# Power_System.net
KiCad netlist of a schematic drawn in Altium Designer
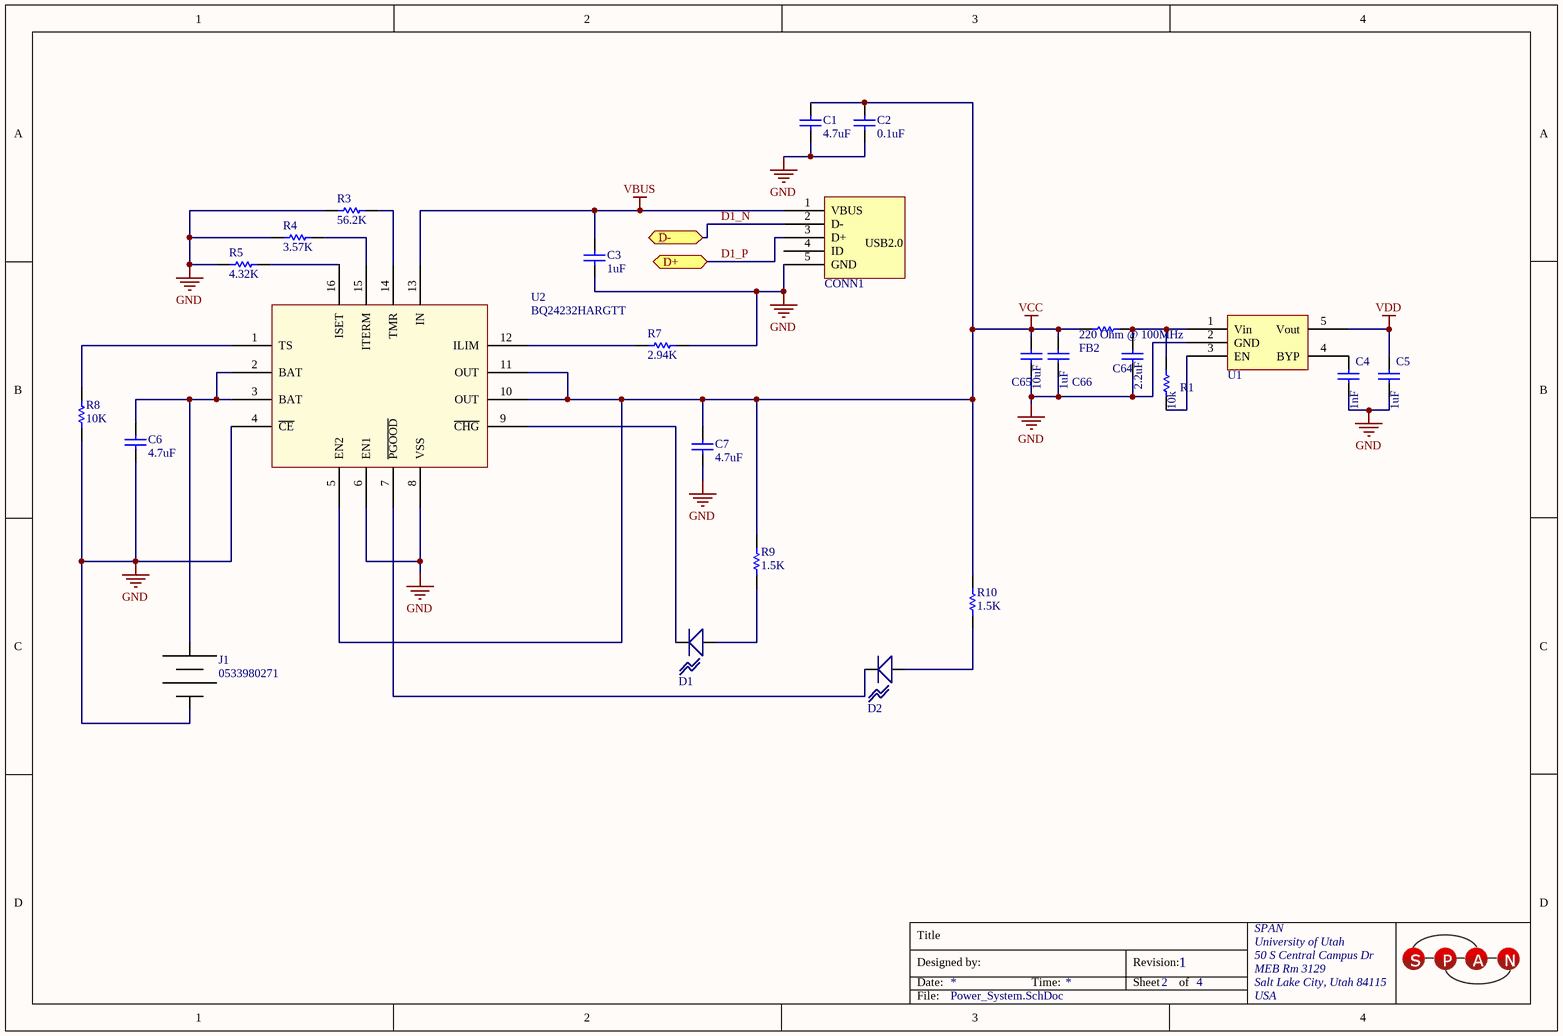
[diagram p0: Power_System.SchDoc]

(export (version "E")
  (design (tool "Eeschema 10.0.6"))
  (components
    (comp (ref "C1")
      (value "4.7uF")
      (footprint "0603_Cap")
      (fields
        (field (name "MANUFACTURER") "Taiyo Yuden")
        (field (name "MANUFACTURER PART NUMBER") "JMK107BJ475MAHT")
        (field (name "TOLERANCE") "±20%")
      )
      (libsource (lib "Sitara") (part "JMK107BJ475MAHT"))
    )
    (comp (ref "C2")
      (value "0.1uF")
      (footprint "0603_Cap")
      (description "CAP CER 0.1UF 16V X7R 0603")
      (fields
        (field (name "MANUFACTURER") "AVX Corporation")
        (field (name "MANUFACTURER PART NUMBER") "0603YC104KAT4A")
      )
      (libsource (lib "Sitara") (part "0603YC104KAT4A"))
    )
    (comp (ref "C3")
      (value "1uF")
      (footprint "0603_Cap")
      (description "CAP CER 1uF SMD")
      (fields
        (field (name "MANUFACTURER") "Taiyo Yuden")
        (field (name "MANUFACTURER PART NUMBER") "JMK107C6105KA-T")
      )
      (libsource (lib "Sitara") (part "JMK107C6105KA-T"))
    )
    (comp (ref "C4")
      (value "10uF")
      (footprint "0603_Cap")
      (description "CAP CER 1000PF 50V 5% NP0 0603")
      (fields
        (field (name "MANUFACTURER") "Murata Electronics North America")
        (field (name "MANUFACTURER PART NUMBER") "GRM1885C1H102JA01D")
      )
      (libsource (lib "Sara") (part "GRM1885C1H102JA01D"))
    )
    (comp (ref "C5")
      (value "GRM188R61A105KA61D")
      (footprint "CAPC1608X08N (0603)")
      (description "CAP CER 1UF 10V 10% X5R 0603")
      (fields
        (field (name "MANUFACTURER") "Murata Electronics North America")
        (field (name "TOLERANCE") "±10%")
      )
      (libsource (lib "Sara") (part "GRM188R61A105KA61D"))
    )
    (comp (ref "C6")
      (value "4.7uF")
      (footprint "0603_Cap")
      (fields
        (field (name "MANUFACTURER") "Taiyo Yuden")
        (field (name "MANUFACTURER PART NUMBER") "JMK107BJ475MAHT")
        (field (name "TOLERANCE") "±20%")
      )
      (libsource (lib "Sitara") (part "JMK107BJ475MAHT"))
    )
    (comp (ref "C7")
      (value "4.7uF")
      (footprint "0603_Cap")
      (fields
        (field (name "MANUFACTURER") "Taiyo Yuden")
        (field (name "MANUFACTURER PART NUMBER") "JMK107BJ475MAHT")
        (field (name "TOLERANCE") "±20%")
      )
      (libsource (lib "Sitara") (part "JMK107BJ475MAHT"))
    )
    (comp (ref "C64")
      (value "GRM188F51A225ZE01D")
      (footprint "CAPC1608X08N (0603)")
      (description "CAP CER 2.2UF 10V Y5V 0603")
      (fields
        (field (name "MANUFACTURER") "Murata Electronics North America")
        (field (name "TOLERANCE") "-20%, +80%")
      )
      (libsource (lib "Sara") (part "GRM188F51A225ZE01D"))
    )
    (comp (ref "C65")
      (value "GRM188R60J106ME47D")
      (footprint "CAPC1608X08N (0603)")
      (description "CAP CER 10UF 6.3V 20% X5R 0603")
      (fields
        (field (name "MANUFACTURER") "Murata Electronics North America")
        (field (name "TOLERANCE") "±20%")
      )
      (libsource (lib "Sara") (part "GRM188R60J106ME47D"))
    )
    (comp (ref "C66")
      (value "GRM188R61A105KA61D")
      (footprint "CAPC1608X08N (0603)")
      (description "CAP CER 1UF 10V 10% X5R 0603")
      (fields
        (field (name "MANUFACTURER") "Murata Electronics North America")
        (field (name "TOLERANCE") "±10%")
      )
      (libsource (lib "Sara") (part "GRM188R61A105KA61D"))
    )
    (comp (ref "CONN1")
      (value "10118193-0001LF")
      (footprint "USB_micro_B")
      (description "CONN USB MICRO B RECPT SMT R/A")
      (fields (field (name "MANUFACTURER") "Amphenol FCI"))
      (libsource (lib "Sitara") (part "10118193-0001LF"))
    )
    (comp (ref "D1")
      (value "LTST-C191KFKT")
      (footprint "0603_LED")
      (description "LED ORANGE CLEAR 0603 SMD")
      (fields (field (name "MANUFACTURER") "Lite-On Inc."))
      (libsource (lib "Sitara") (part "LTST-C191KFKT"))
    )
    (comp (ref "D2")
      (value "LTST-C191KFKT")
      (footprint "0603_LED")
      (description "LED ORANGE CLEAR 0603 SMD")
      (fields (field (name "MANUFACTURER") "Lite-On Inc."))
      (libsource (lib "Sitara") (part "LTST-C191KFKT"))
    )
    (comp (ref "FB2")
      (value "BLM18BD221SN1D")
      (footprint "RESC1608X06N (0603)")
      (description "FERRITE CHIP 220 OHM 200MA 0603")
      (fields (field (name "MANUFACTURER") "Murata Electronics North America"))
      (libsource (lib "Sara") (part "BLM18BD221SN1D"))
    )
    (comp (ref "J1")
      (value "0533980271")
      (footprint "53398-0271")
      (description "CONN HEADER 2POS 1.25MM VERT SMD")
      (fields
        (field (name "MANUFACTURER") "Molex Inc")
        (field (name "MANUFACTURER PART NUMBER") "0533980271")
      )
      (libsource (lib "Chronos") (part "0533980271"))
    )
    (comp (ref "R1")
      (value "10K")
      (footprint "0603_RES")
      (description "RES 10.0K OHM 1/10W 1% 0603 SMD")
      (fields
        (field (name "MANUFACTURER") "Yageo")
        (field (name "MANUFACTURER PART NUMBER") "RC0603FR-0710KL")
      )
      (libsource (lib "Sara") (part "RC0603FR-0710KL"))
    )
    (comp (ref "R3")
      (value "56.2K")
      (footprint "0603_RES")
      (description "RES SMD 56.2KOHM 0.1% 1/10W 0603")
      (fields
        (field (name "MANUFACTURER") "Panasonic Electronic Components")
        (field (name "MANUFACTURER PART NUMBER") "ERA-3AEB5622V")
      )
      (libsource (lib "Sitara") (part "ERA-3AEB5622V"))
    )
    (comp (ref "R4")
      (value "3.57K")
      (footprint "0603_RES")
      (description "RES SMD 3.57KOHM 0.1% 1/10W 0603")
      (fields
        (field (name "MANUFACTURER") "Vishay Dale")
        (field (name "MANUFACTURER PART NUMBER") "TNPW06033K57BEEA")
      )
      (libsource (lib "Sitara") (part "TNPW06033K57BEEA"))
    )
    (comp (ref "R5")
      (value "4.32K")
      (footprint "0603_RES")
      (description "RES SMD 4.32KOHM 0.1% 1/10W 0603")
      (fields
        (field (name "MANUFACTURER") "Panasonic Electronic Components")
        (field (name "MANUFACTURER PART NUMBER") "ERA-3AEB4321V")
      )
      (libsource (lib "Sitara") (part "ERA-3AEB4321V"))
    )
    (comp (ref "R7")
      (value "2.94K")
      (footprint "0603_RES")
      (description "RES SMD 2.94KOHM 0.1% 1/10W 0603")
      (fields
        (field (name "MANUFACTURER") "Panasonic Electronic Components")
        (field (name "MANUFACTURER PART NUMBER") "ERA-3AEB2941V")
      )
      (libsource (lib "Sitara") (part "ERA-3AEB2941V"))
    )
    (comp (ref "R8")
      (value "10K")
      (footprint "0603_RES")
      (description "RES SMD 10KOHM 0.1% 0.0375W 0603")
      (fields
        (field (name "MANUFACTURER") "Vishay Sfernice")
        (field (name "MANUFACTURER PART NUMBER") "PHT0603Y1002BGT200")
      )
      (libsource (lib "Sitara") (part "PHT0603Y1002BGT200"))
    )
    (comp (ref "R9")
      (value "1.5K")
      (footprint "0603_RES")
      (description "RES SMD 1.5K OHM 5% 1/10W 0603")
      (fields
        (field (name "MANUFACTURER") "Vishay Dale")
        (field (name "MANUFACTURER PART NUMBER") "CRCW06031K50JNEA")
      )
      (libsource (lib "Sitara") (part "CRCW06031K50JNEA"))
    )
    (comp (ref "R10")
      (value "1.5K")
      (footprint "0603_RES")
      (description "RES SMD 1.5K OHM 5% 1/10W 0603")
      (fields
        (field (name "MANUFACTURER") "Vishay Dale")
        (field (name "MANUFACTURER PART NUMBER") "CRCW06031K50JNEA")
      )
      (libsource (lib "Sitara") (part "CRCW06031K50JNEA"))
    )
    (comp (ref "U1")
      (value "TPS2147IDGQG4")
      (footprint "SOT95P280X145-5N")
      (description "IC REG LDO 3V 0.1A SOT23-5")
      (fields
        (field (name "MANUFACTURER") "Fairchild Semiconductor")
        (field (name "MANUFACTURER PART NUMBER") "FAN2500S30X")
      )
      (libsource (lib "Sara") (part "FAN2500S30X"))
    )
    (comp (ref "U2")
      (value "BQ24232HARGTT")
      (footprint "QFN_16_BQ24232")
      (description "IC LI-ION CHARGE PWR MGMT 16VQFN")
      (fields (field (name "MANUFACTURER") "Texas Instruments"))
      (libsource (lib "Sitara") (part "BQ24232HARGTT"))
    )
  )
  (nets
    (net (code "1") (name "/D1_N") (class "Default")
      (node (ref "CONN1") (pin "2") (pinfunction "D-_2") (pintype "passive"))
    )
    (net (code "2") (name "/D1_P") (class "Default")
      (node (ref "CONN1") (pin "3") (pinfunction "D+_3") (pintype "passive"))
    )
    (net (code "3") (name "GND") (class "Default")
      (node (ref "C1") (pin "1") (pinfunction "1_1") (pintype "passive"))
      (node (ref "C2") (pin "1") (pinfunction "1_1") (pintype "passive"))
      (node (ref "C3") (pin "1") (pinfunction "1_1") (pintype "passive"))
      (node (ref "C4") (pin "1") (pinfunction "1_1") (pintype "passive"))
      (node (ref "C5") (pin "1") (pinfunction "1_1") (pintype "passive"))
      (node (ref "C6") (pin "1") (pinfunction "1_1") (pintype "passive"))
      (node (ref "C64") (pin "1") (pinfunction "1_1") (pintype "passive"))
      (node (ref "C65") (pin "1") (pinfunction "1_1") (pintype "passive"))
      (node (ref "C66") (pin "1") (pinfunction "1_1") (pintype "passive"))
      (node (ref "C7") (pin "1") (pinfunction "1_1") (pintype "passive"))
      (node (ref "CONN1") (pin "5") (pinfunction "GND_5") (pintype "passive"))
      (node (ref "J1") (pin "2") (pinfunction "Neg_2") (pintype "passive"))
      (node (ref "R3") (pin "1") (pinfunction "1_1") (pintype "passive"))
      (node (ref "R4") (pin "1") (pinfunction "1_1") (pintype "passive"))
      (node (ref "R5") (pin "1") (pinfunction "1_1") (pintype "passive"))
      (node (ref "R7") (pin "2") (pinfunction "2_2") (pintype "passive"))
      (node (ref "R8") (pin "1") (pinfunction "1_1") (pintype "passive"))
      (node (ref "U1") (pin "2") (pinfunction "GND_2") (pintype "passive"))
      (node (ref "U2") (pin "4") (pinfunction "~{CE}_4") (pintype "passive"))
      (node (ref "U2") (pin "6") (pinfunction "EN1_6") (pintype "passive"))
      (node (ref "U2") (pin "8") (pinfunction "VSS_8") (pintype "passive"))
    )
    (net (code "4") (name "Net-(D1-Pad1)") (class "Default")
      (node (ref "D1") (pin "1") (pinfunction "1_1") (pintype "passive"))
      (node (ref "R9") (pin "1") (pinfunction "1_1") (pintype "passive"))
    )
    (net (code "5") (name "Net-(D2-Pad1)") (class "Default")
      (node (ref "D2") (pin "1") (pinfunction "1_1") (pintype "passive"))
      (node (ref "R10") (pin "1") (pinfunction "1_1") (pintype "passive"))
    )
    (net (code "6") (name "Net-(J1-Pos)") (class "Default")
      (node (ref "C6") (pin "2") (pinfunction "2_2") (pintype "passive"))
      (node (ref "J1") (pin "1") (pinfunction "Pos_1") (pintype "passive"))
      (node (ref "U2") (pin "2") (pinfunction "BAT_2") (pintype "passive"))
      (node (ref "U2") (pin "3") (pinfunction "BAT_3") (pintype "passive"))
    )
    (net (code "7") (name "Net-(U1-BYP)") (class "Default")
      (node (ref "C4") (pin "2") (pinfunction "2_2") (pintype "passive"))
      (node (ref "U1") (pin "4") (pinfunction "BYP_4") (pintype "passive"))
    )
    (net (code "8") (name "Net-(U1-EN)") (class "Default")
      (node (ref "R1") (pin "1") (pinfunction "1_1") (pintype "passive"))
      (node (ref "U1") (pin "3") (pinfunction "EN_3") (pintype "passive"))
    )
    (net (code "9") (name "Net-(U1-Vin)") (class "Default")
      (node (ref "C64") (pin "2") (pinfunction "2_2") (pintype "passive"))
      (node (ref "FB2") (pin "2") (pinfunction "2_2") (pintype "passive"))
      (node (ref "R1") (pin "2") (pinfunction "2_2") (pintype "passive"))
      (node (ref "U1") (pin "1") (pinfunction "Vin_1") (pintype "passive"))
    )
    (net (code "10") (name "Net-(U2-ILIM)") (class "Default")
      (node (ref "R7") (pin "1") (pinfunction "1_1") (pintype "passive"))
      (node (ref "U2") (pin "12") (pinfunction "ILIM_12") (pintype "passive"))
    )
    (net (code "11") (name "Net-(U2-ISET)") (class "Default")
      (node (ref "R5") (pin "2") (pinfunction "2_2") (pintype "passive"))
      (node (ref "U2") (pin "16") (pinfunction "ISET_16") (pintype "passive"))
    )
    (net (code "12") (name "Net-(U2-ITERM)") (class "Default")
      (node (ref "R4") (pin "2") (pinfunction "2_2") (pintype "passive"))
      (node (ref "U2") (pin "15") (pinfunction "ITERM_15") (pintype "passive"))
    )
    (net (code "13") (name "Net-(U2-TMR)") (class "Default")
      (node (ref "R3") (pin "2") (pinfunction "2_2") (pintype "passive"))
      (node (ref "U2") (pin "14") (pinfunction "TMR_14") (pintype "passive"))
    )
    (net (code "14") (name "Net-(U2-TS)") (class "Default")
      (node (ref "R8") (pin "2") (pinfunction "2_2") (pintype "passive"))
      (node (ref "U2") (pin "1") (pinfunction "TS_1") (pintype "passive"))
    )
    (net (code "15") (name "Net-(U2-~{CHG})") (class "Default")
      (node (ref "D1") (pin "2") (pinfunction "2_2") (pintype "passive"))
      (node (ref "U2") (pin "9") (pinfunction "~{CHG}_9") (pintype "passive"))
    )
    (net (code "16") (name "Net-(U2-~{PGOOD})") (class "Default")
      (node (ref "D2") (pin "2") (pinfunction "2_2") (pintype "passive"))
      (node (ref "U2") (pin "7") (pinfunction "~{PGOOD}_7") (pintype "passive"))
    )
    (net (code "17") (name "VBUS") (class "Default")
      (node (ref "C3") (pin "2") (pinfunction "2_2") (pintype "passive"))
      (node (ref "CONN1") (pin "1") (pinfunction "VBUS_1") (pintype "passive"))
      (node (ref "U2") (pin "13") (pinfunction "IN_13") (pintype "passive"))
    )
    (net (code "18") (name "VCC") (class "Default")
      (node (ref "C1") (pin "2") (pinfunction "2_2") (pintype "passive"))
      (node (ref "C2") (pin "2") (pinfunction "2_2") (pintype "passive"))
      (node (ref "C65") (pin "2") (pinfunction "2_2") (pintype "passive"))
      (node (ref "C66") (pin "2") (pinfunction "2_2") (pintype "passive"))
      (node (ref "C7") (pin "2") (pinfunction "2_2") (pintype "passive"))
      (node (ref "FB2") (pin "1") (pinfunction "1_1") (pintype "passive"))
      (node (ref "R10") (pin "2") (pinfunction "2_2") (pintype "passive"))
      (node (ref "R9") (pin "2") (pinfunction "2_2") (pintype "passive"))
      (node (ref "U2") (pin "10") (pinfunction "OUT_10") (pintype "passive"))
      (node (ref "U2") (pin "11") (pinfunction "OUT_11") (pintype "passive"))
      (node (ref "U2") (pin "5") (pinfunction "EN2_5") (pintype "passive"))
    )
    (net (code "19") (name "VDD") (class "Default")
      (node (ref "C5") (pin "2") (pinfunction "2_2") (pintype "passive"))
      (node (ref "U1") (pin "5") (pinfunction "Vout_5") (pintype "passive"))
    )
    (net (code "20") (name "unconnected-(CONN1-ID-Pad4)") (class "Default")
      (node (ref "CONN1") (pin "4") (pinfunction "ID_4") (pintype "passive"))
    )
  )
)
